# logicBlocks-OR.net
KiCad netlist of a schematic drawn in EAGLE
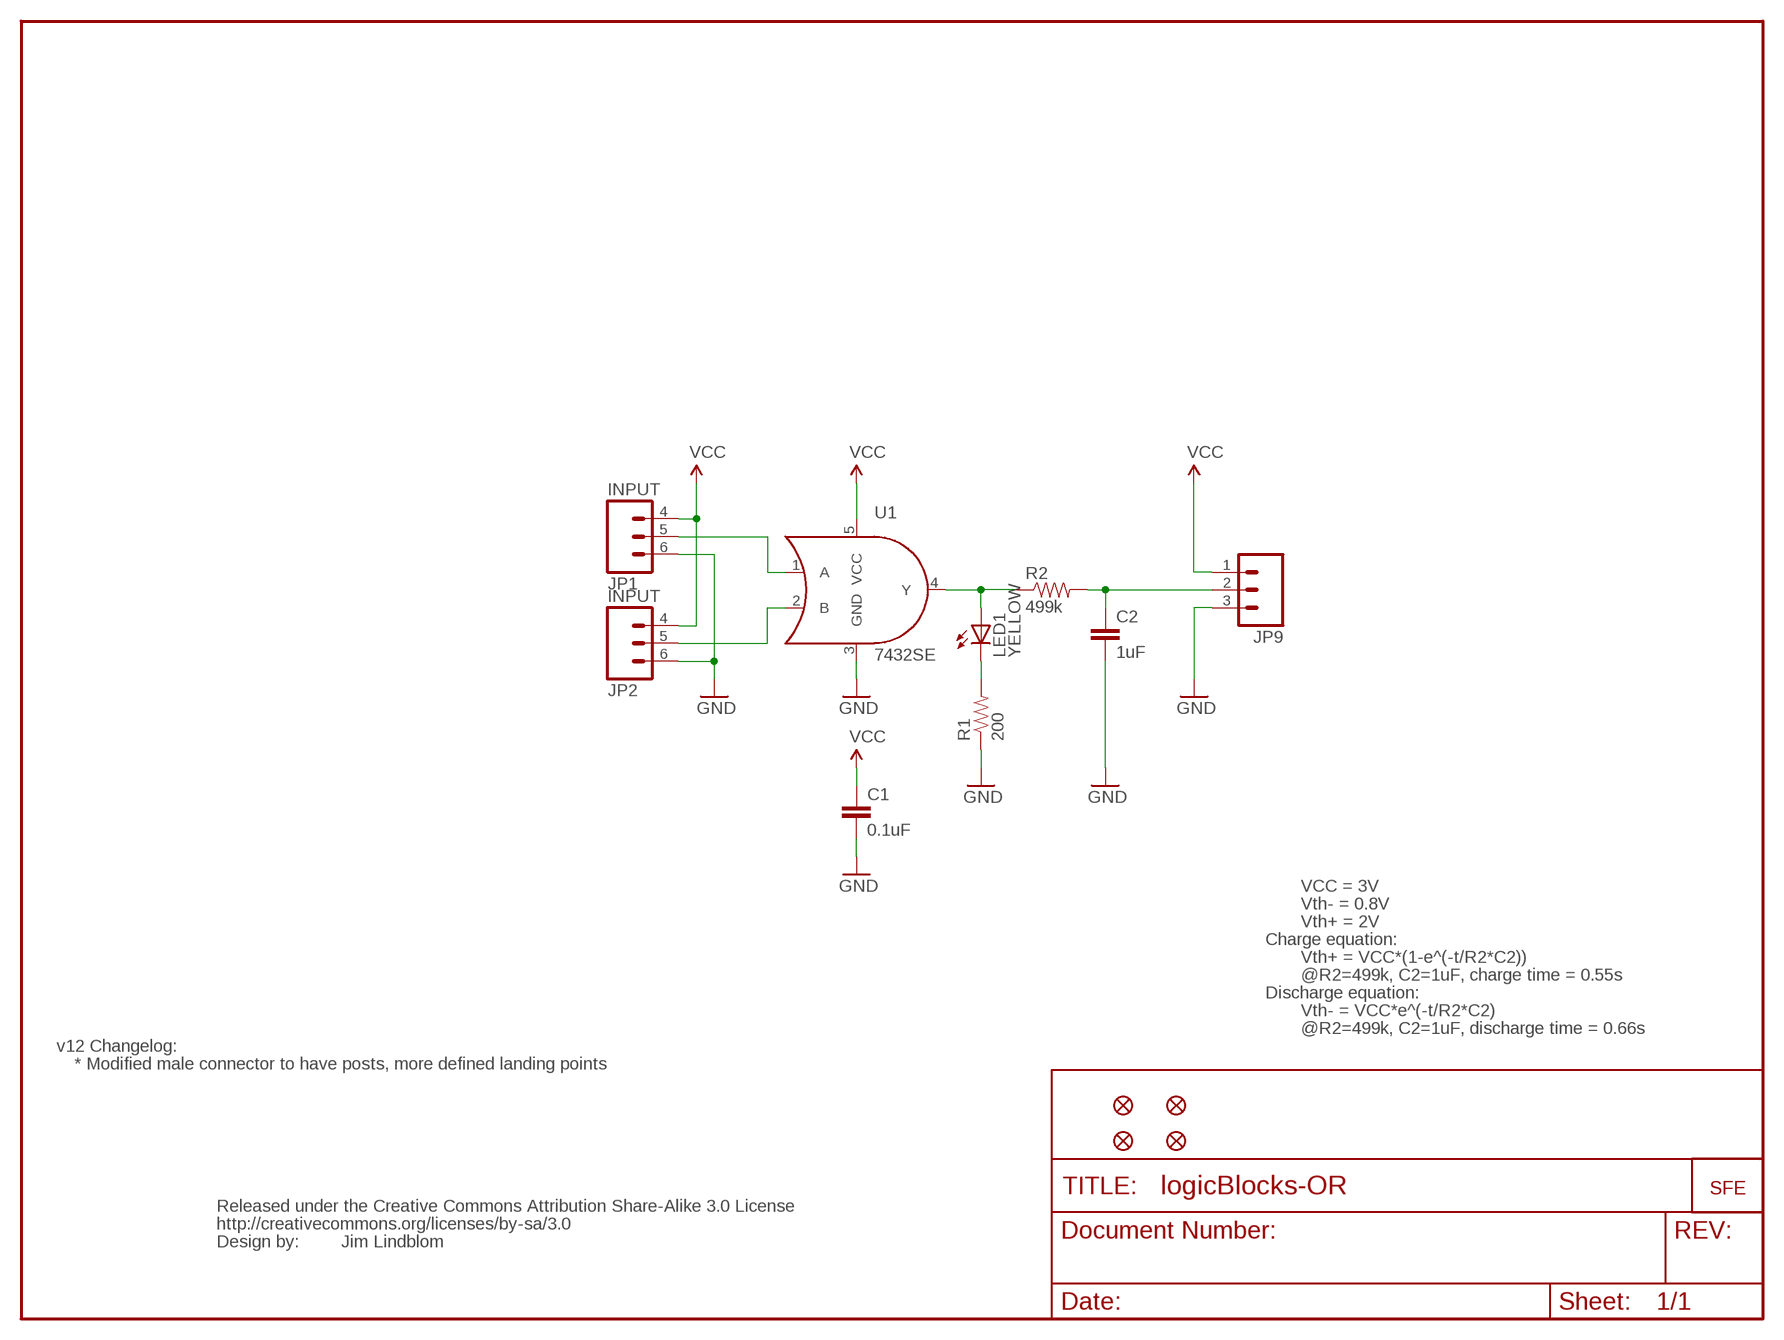
[diagram p0: schematic, sheet 1]

(export (version "E")
  (design (tool "Eeschema 10.0.6"))
  (components
    (comp (ref "C1")
      (value "0.1uF")
      (footprint "eagle-import:0402-CAP")
      (libsource (lib "eagle-import") (part "CAP0402-CAP"))
    )
    (comp (ref "C2")
      (value "1uF")
      (footprint "eagle-import:0402-CAP")
      (libsource (lib "eagle-import") (part "CAP0402-CAP"))
    )
    (comp (ref "JP1")
      (value "INPUT")
      (footprint "eagle-import:1X03-SMD-FEMALE")
      (libsource (lib "eagle-import") (part "M03SMD-RA-FEMALE"))
    )
    (comp (ref "JP2")
      (value "INPUT")
      (footprint "eagle-import:1X03-SMD-FEMALE")
      (libsource (lib "eagle-import") (part "M03SMD-RA-FEMALE"))
    )
    (comp (ref "JP4")
      (value "LOGO-SFESK")
      (footprint "eagle-import:SFE-LOGO-FLAME")
      (libsource (lib "eagle-import") (part "LOGO-SFESK"))
    )
    (comp (ref "JP5")
      (value "FIDUCIALUFIDUCIAL")
      (footprint "eagle-import:MICRO-FIDUCIAL")
      (libsource (lib "eagle-import") (part "FIDUCIALUFIDUCIAL"))
    )
    (comp (ref "JP6")
      (value "FIDUCIALUFIDUCIAL")
      (footprint "eagle-import:MICRO-FIDUCIAL")
      (libsource (lib "eagle-import") (part "FIDUCIALUFIDUCIAL"))
    )
    (comp (ref "JP7")
      (value "FIDUCIALUFIDUCIAL")
      (footprint "eagle-import:MICRO-FIDUCIAL")
      (libsource (lib "eagle-import") (part "FIDUCIALUFIDUCIAL"))
    )
    (comp (ref "JP8")
      (value "FIDUCIALUFIDUCIAL")
      (footprint "eagle-import:MICRO-FIDUCIAL")
      (libsource (lib "eagle-import") (part "FIDUCIALUFIDUCIAL"))
    )
    (comp (ref "JP9")
      (value "M03SMD_RA_MALE_POST")
      (footprint "eagle-import:1X03_SMD_RA_MALE_POST")
      (libsource (lib "eagle-import") (part "M03SMD_RA_MALE_POST"))
    )
    (comp (ref "LED1")
      (value "YELLOW")
      (footprint "eagle-import:LED-1206")
      (libsource (lib "eagle-import") (part "LED1206"))
    )
    (comp (ref "R1")
      (value "200")
      (footprint "eagle-import:0402-RES")
      (libsource (lib "eagle-import") (part "RESISTOR0402-RES"))
    )
    (comp (ref "R2")
      (value "499k")
      (footprint "eagle-import:0402-RES")
      (libsource (lib "eagle-import") (part "RESISTOR0402-RES"))
    )
    (comp (ref "U$2")
      (value "CREATIVE_COMMONS")
      (footprint "eagle-import:CREATIVE_COMMONS")
      (libsource (lib "eagle-import") (part "CREATIVE_COMMONS"))
    )
    (comp (ref "U1")
      (value "7432SE")
      (footprint "eagle-import:SOT353")
      (libsource (lib "eagle-import") (part "7432SE"))
    )
  )
  (nets
    (net (code "1") (name "GND") (class "Default")
      (node (ref "C1") (pin "2") (pinfunction "2_2") (pintype "passive"))
      (node (ref "C2") (pin "2") (pinfunction "2_2") (pintype "passive"))
      (node (ref "JP1") (pin "6") (pinfunction "3_6") (pintype "passive"))
      (node (ref "JP2") (pin "6") (pinfunction "3_6") (pintype "passive"))
      (node (ref "JP9") (pin "3") (pinfunction "3_3") (pintype "passive"))
      (node (ref "R1") (pin "1") (pinfunction "1_1") (pintype "passive"))
      (node (ref "U1") (pin "3") (pinfunction "GND_3") (pintype "bidirectional"))
    )
    (net (code "2") (name "Net-(C2-Pad1)") (class "Default")
      (node (ref "C2") (pin "1") (pinfunction "1_1") (pintype "passive"))
      (node (ref "JP9") (pin "2") (pinfunction "2_2") (pintype "passive"))
      (node (ref "R2") (pin "2") (pinfunction "2_2") (pintype "passive"))
    )
    (net (code "3") (name "Net-(JP1-2)") (class "Default")
      (node (ref "JP1") (pin "5") (pinfunction "2_5") (pintype "passive"))
      (node (ref "U1") (pin "1") (pinfunction "A_1") (pintype "bidirectional"))
    )
    (net (code "4") (name "Net-(JP2-2)") (class "Default")
      (node (ref "JP2") (pin "5") (pinfunction "2_5") (pintype "passive"))
      (node (ref "U1") (pin "2") (pinfunction "B_2") (pintype "bidirectional"))
    )
    (net (code "5") (name "Net-(LED1-PadC)") (class "Default")
      (node (ref "LED1") (pin "C") (pinfunction "C_C") (pintype "passive"))
      (node (ref "R1") (pin "2") (pinfunction "2_2") (pintype "passive"))
    )
    (net (code "6") (name "Net-(U1-Y)") (class "Default")
      (node (ref "LED1") (pin "A") (pinfunction "A_A") (pintype "passive"))
      (node (ref "R2") (pin "1") (pinfunction "1_1") (pintype "passive"))
      (node (ref "U1") (pin "4") (pinfunction "Y_4") (pintype "bidirectional"))
    )
    (net (code "7") (name "VCC") (class "Default")
      (node (ref "C1") (pin "1") (pinfunction "1_1") (pintype "passive"))
      (node (ref "JP1") (pin "4") (pinfunction "1_4") (pintype "passive"))
      (node (ref "JP2") (pin "4") (pinfunction "1_4") (pintype "passive"))
      (node (ref "JP9") (pin "1") (pinfunction "1_1") (pintype "passive"))
      (node (ref "U1") (pin "5") (pinfunction "VCC_5") (pintype "bidirectional"))
    )
  )
)
